# Bus_Solar_V2_Packed_with_pads.net
KiCad netlist of a schematic drawn in EAGLE
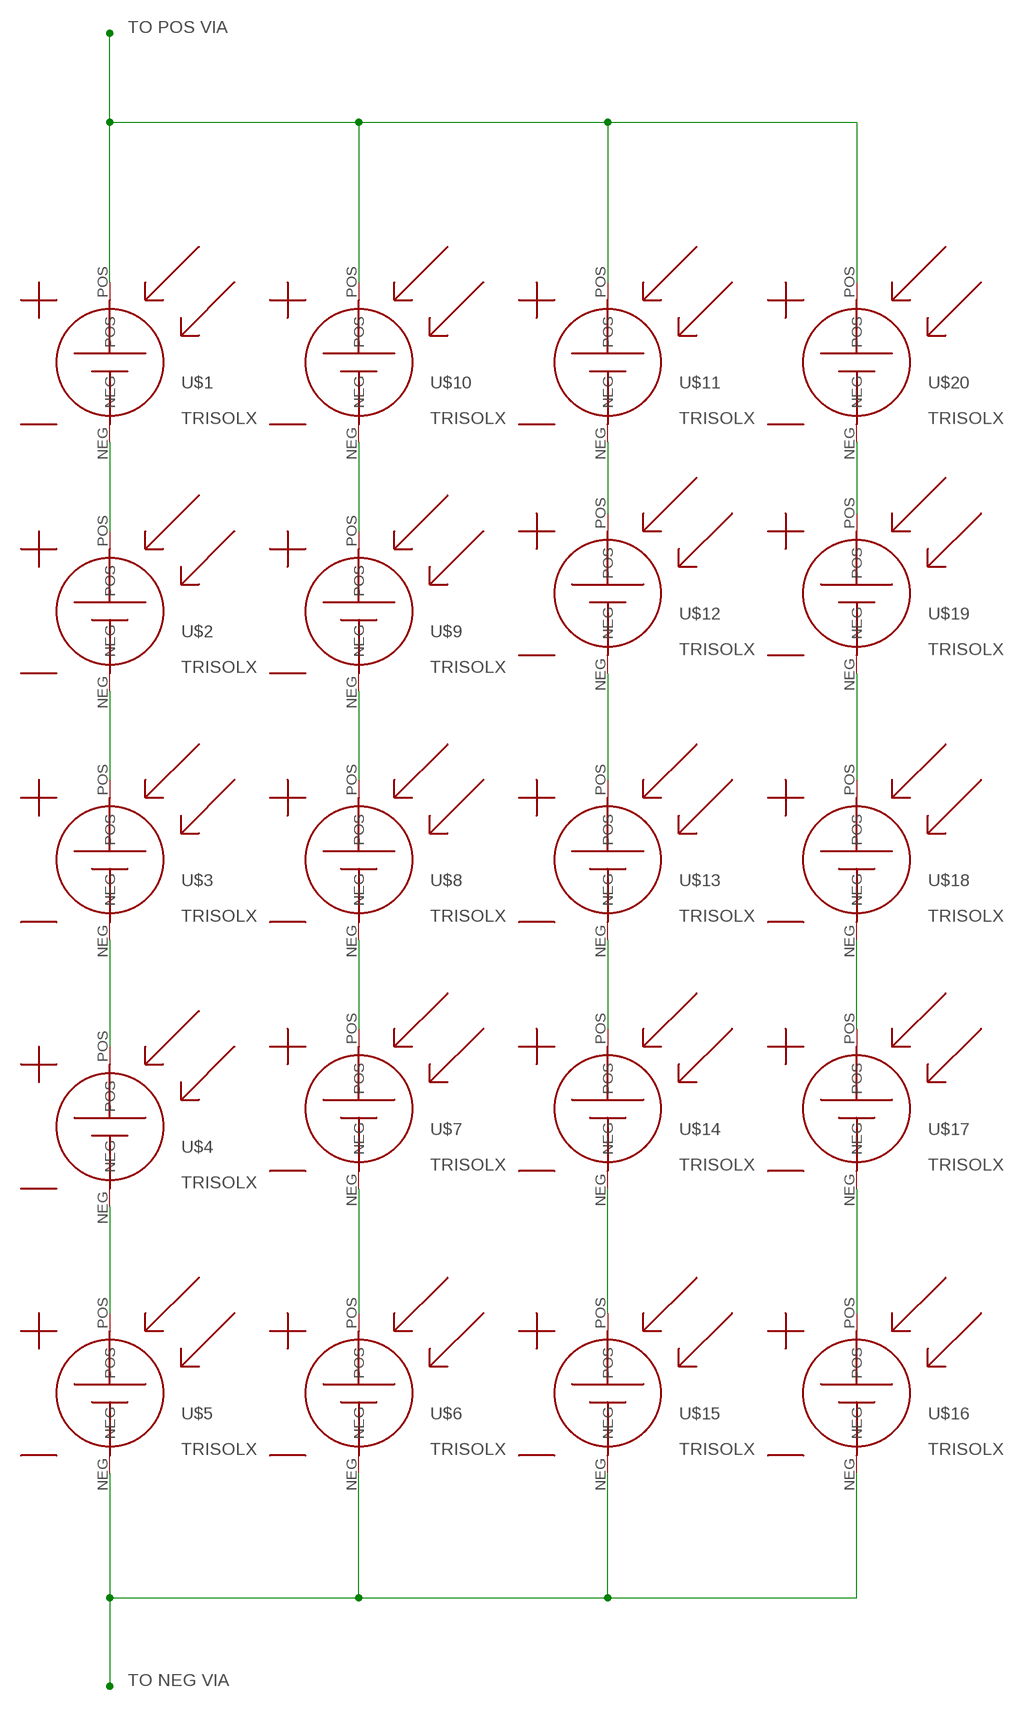
[diagram p0: schematic, sheet 1]

(export (version "E")
  (design (tool "Eeschema 10.0.6"))
  (components
    (comp (ref "U$1")
      (value "TRISOLX")
      (footprint "eagle-import:TRISOLX")
      (libsource (lib "eagle-import") (part "TRISOLX"))
    )
    (comp (ref "U$2")
      (value "TRISOLX")
      (footprint "eagle-import:TRISOLX")
      (libsource (lib "eagle-import") (part "TRISOLX"))
    )
    (comp (ref "U$3")
      (value "TRISOLX")
      (footprint "eagle-import:TRISOLX")
      (libsource (lib "eagle-import") (part "TRISOLX"))
    )
    (comp (ref "U$4")
      (value "TRISOLX")
      (footprint "eagle-import:TRISOLX")
      (libsource (lib "eagle-import") (part "TRISOLX"))
    )
    (comp (ref "U$5")
      (value "TRISOLX")
      (footprint "eagle-import:TRISOLX")
      (libsource (lib "eagle-import") (part "TRISOLX"))
    )
    (comp (ref "U$6")
      (value "TRISOLX")
      (footprint "eagle-import:TRISOLX")
      (libsource (lib "eagle-import") (part "TRISOLX"))
    )
    (comp (ref "U$7")
      (value "TRISOLX")
      (footprint "eagle-import:TRISOLX")
      (libsource (lib "eagle-import") (part "TRISOLX"))
    )
    (comp (ref "U$8")
      (value "TRISOLX")
      (footprint "eagle-import:TRISOLX")
      (libsource (lib "eagle-import") (part "TRISOLX"))
    )
    (comp (ref "U$9")
      (value "TRISOLX")
      (footprint "eagle-import:TRISOLX")
      (libsource (lib "eagle-import") (part "TRISOLX"))
    )
    (comp (ref "U$10")
      (value "TRISOLX")
      (footprint "eagle-import:TRISOLX")
      (libsource (lib "eagle-import") (part "TRISOLX"))
    )
    (comp (ref "U$11")
      (value "TRISOLX")
      (footprint "eagle-import:TRISOLX")
      (libsource (lib "eagle-import") (part "TRISOLX"))
    )
    (comp (ref "U$12")
      (value "TRISOLX")
      (footprint "eagle-import:TRISOLX")
      (libsource (lib "eagle-import") (part "TRISOLX"))
    )
    (comp (ref "U$13")
      (value "TRISOLX")
      (footprint "eagle-import:TRISOLX")
      (libsource (lib "eagle-import") (part "TRISOLX"))
    )
    (comp (ref "U$14")
      (value "TRISOLX")
      (footprint "eagle-import:TRISOLX")
      (libsource (lib "eagle-import") (part "TRISOLX"))
    )
    (comp (ref "U$15")
      (value "TRISOLX")
      (footprint "eagle-import:TRISOLX")
      (libsource (lib "eagle-import") (part "TRISOLX"))
    )
    (comp (ref "U$16")
      (value "TRISOLX")
      (footprint "eagle-import:TRISOLX")
      (libsource (lib "eagle-import") (part "TRISOLX"))
    )
    (comp (ref "U$17")
      (value "TRISOLX")
      (footprint "eagle-import:TRISOLX")
      (libsource (lib "eagle-import") (part "TRISOLX"))
    )
    (comp (ref "U$18")
      (value "TRISOLX")
      (footprint "eagle-import:TRISOLX")
      (libsource (lib "eagle-import") (part "TRISOLX"))
    )
    (comp (ref "U$19")
      (value "TRISOLX")
      (footprint "eagle-import:TRISOLX")
      (libsource (lib "eagle-import") (part "TRISOLX"))
    )
    (comp (ref "U$20")
      (value "TRISOLX")
      (footprint "eagle-import:TRISOLX")
      (libsource (lib "eagle-import") (part "TRISOLX"))
    )
  )
  (nets
    (net (code "1") (name "Net-(U$1-PadNEG)") (class "Default")
      (node (ref "U$1") (pin "NEG") (pinfunction "NEG_NEG") (pintype "bidirectional"))
      (node (ref "U$2") (pin "POS") (pinfunction "POS_POS") (pintype "bidirectional"))
    )
    (net (code "2") (name "Net-(U$1-PadPOS)") (class "Default")
      (node (ref "U$1") (pin "POS") (pinfunction "POS_POS") (pintype "bidirectional"))
      (node (ref "U$10") (pin "POS") (pinfunction "POS_POS") (pintype "bidirectional"))
      (node (ref "U$11") (pin "POS") (pinfunction "POS_POS") (pintype "bidirectional"))
      (node (ref "U$20") (pin "POS") (pinfunction "POS_POS") (pintype "bidirectional"))
    )
    (net (code "3") (name "Net-(U$2-PadNEG)") (class "Default")
      (node (ref "U$2") (pin "NEG") (pinfunction "NEG_NEG") (pintype "bidirectional"))
      (node (ref "U$3") (pin "POS") (pinfunction "POS_POS") (pintype "bidirectional"))
    )
    (net (code "4") (name "Net-(U$3-PadNEG)") (class "Default")
      (node (ref "U$3") (pin "NEG") (pinfunction "NEG_NEG") (pintype "bidirectional"))
      (node (ref "U$4") (pin "POS") (pinfunction "POS_POS") (pintype "bidirectional"))
    )
    (net (code "5") (name "Net-(U$4-PadNEG)") (class "Default")
      (node (ref "U$4") (pin "NEG") (pinfunction "NEG_NEG") (pintype "bidirectional"))
      (node (ref "U$5") (pin "POS") (pinfunction "POS_POS") (pintype "bidirectional"))
    )
    (net (code "6") (name "Net-(U$6-PadPOS)") (class "Default")
      (node (ref "U$6") (pin "POS") (pinfunction "POS_POS") (pintype "bidirectional"))
      (node (ref "U$7") (pin "NEG") (pinfunction "NEG_NEG") (pintype "bidirectional"))
    )
    (net (code "7") (name "Net-(U$7-PadPOS)") (class "Default")
      (node (ref "U$7") (pin "POS") (pinfunction "POS_POS") (pintype "bidirectional"))
      (node (ref "U$8") (pin "NEG") (pinfunction "NEG_NEG") (pintype "bidirectional"))
    )
    (net (code "8") (name "Net-(U$8-PadPOS)") (class "Default")
      (node (ref "U$8") (pin "POS") (pinfunction "POS_POS") (pintype "bidirectional"))
      (node (ref "U$9") (pin "NEG") (pinfunction "NEG_NEG") (pintype "bidirectional"))
    )
    (net (code "9") (name "Net-(U$10-PadNEG)") (class "Default")
      (node (ref "U$10") (pin "NEG") (pinfunction "NEG_NEG") (pintype "bidirectional"))
      (node (ref "U$9") (pin "POS") (pinfunction "POS_POS") (pintype "bidirectional"))
    )
    (net (code "10") (name "Net-(U$11-PadNEG)") (class "Default")
      (node (ref "U$11") (pin "NEG") (pinfunction "NEG_NEG") (pintype "bidirectional"))
      (node (ref "U$12") (pin "POS") (pinfunction "POS_POS") (pintype "bidirectional"))
    )
    (net (code "11") (name "Net-(U$12-PadNEG)") (class "Default")
      (node (ref "U$12") (pin "NEG") (pinfunction "NEG_NEG") (pintype "bidirectional"))
      (node (ref "U$13") (pin "POS") (pinfunction "POS_POS") (pintype "bidirectional"))
    )
    (net (code "12") (name "Net-(U$13-PadNEG)") (class "Default")
      (node (ref "U$13") (pin "NEG") (pinfunction "NEG_NEG") (pintype "bidirectional"))
      (node (ref "U$14") (pin "POS") (pinfunction "POS_POS") (pintype "bidirectional"))
    )
    (net (code "13") (name "Net-(U$14-PadNEG)") (class "Default")
      (node (ref "U$14") (pin "NEG") (pinfunction "NEG_NEG") (pintype "bidirectional"))
      (node (ref "U$15") (pin "POS") (pinfunction "POS_POS") (pintype "bidirectional"))
    )
    (net (code "14") (name "Net-(U$15-PadNEG)") (class "Default")
      (node (ref "U$15") (pin "NEG") (pinfunction "NEG_NEG") (pintype "bidirectional"))
      (node (ref "U$16") (pin "NEG") (pinfunction "NEG_NEG") (pintype "bidirectional"))
      (node (ref "U$5") (pin "NEG") (pinfunction "NEG_NEG") (pintype "bidirectional"))
      (node (ref "U$6") (pin "NEG") (pinfunction "NEG_NEG") (pintype "bidirectional"))
    )
    (net (code "15") (name "Net-(U$16-PadPOS)") (class "Default")
      (node (ref "U$16") (pin "POS") (pinfunction "POS_POS") (pintype "bidirectional"))
      (node (ref "U$17") (pin "NEG") (pinfunction "NEG_NEG") (pintype "bidirectional"))
    )
    (net (code "16") (name "Net-(U$17-PadPOS)") (class "Default")
      (node (ref "U$17") (pin "POS") (pinfunction "POS_POS") (pintype "bidirectional"))
      (node (ref "U$18") (pin "NEG") (pinfunction "NEG_NEG") (pintype "bidirectional"))
    )
    (net (code "17") (name "Net-(U$18-PadPOS)") (class "Default")
      (node (ref "U$18") (pin "POS") (pinfunction "POS_POS") (pintype "bidirectional"))
      (node (ref "U$19") (pin "NEG") (pinfunction "NEG_NEG") (pintype "bidirectional"))
    )
    (net (code "18") (name "Net-(U$19-PadPOS)") (class "Default")
      (node (ref "U$19") (pin "POS") (pinfunction "POS_POS") (pintype "bidirectional"))
      (node (ref "U$20") (pin "NEG") (pinfunction "NEG_NEG") (pintype "bidirectional"))
    )
  )
)
